# Nu6550.net
KiCad netlist of a schematic drawn in EAGLE
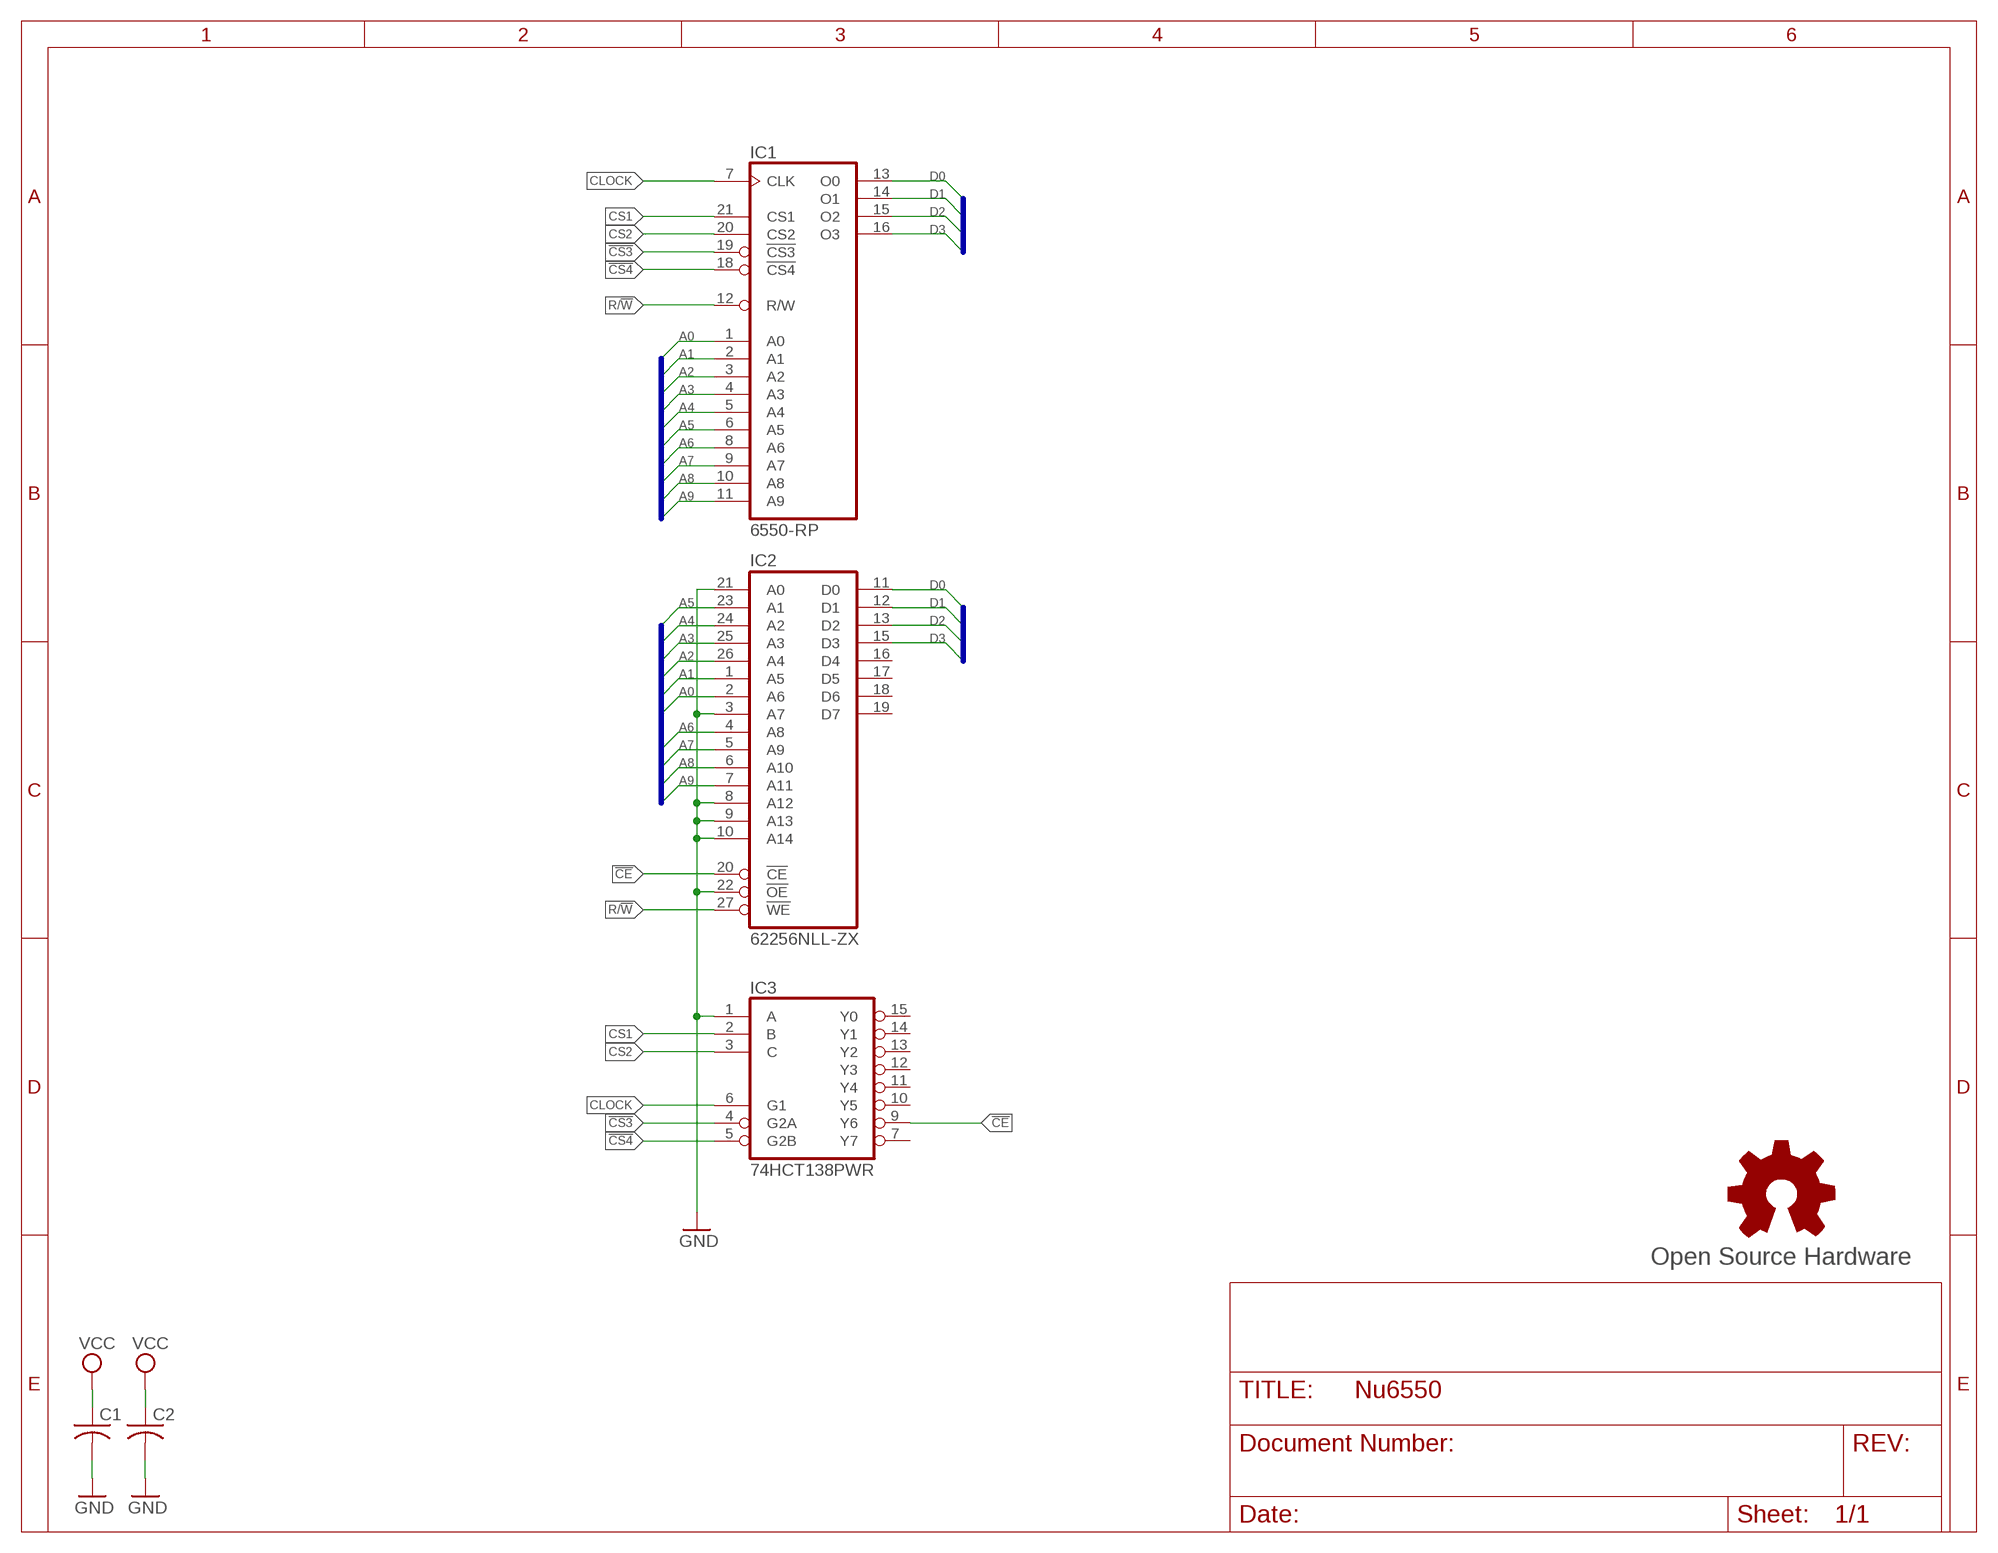
[diagram p0: schematic, sheet 1]

(export (version "E")
  (design (tool "Eeschema 10.0.6"))
  (components
    (comp (ref "C1")
      (value "C-USC0402")
      (footprint "eagle-import:C0402")
      (libsource (lib "eagle-import") (part "C-USC0402"))
    )
    (comp (ref "C2")
      (value "C-USC0402")
      (footprint "eagle-import:C0402")
      (libsource (lib "eagle-import") (part "C-USC0402"))
    )
    (comp (ref "GOLD_ORB_SM1")
      (value "Open Source Hardware")
      (footprint "eagle-import:OSHW_5MM")
      (libsource (lib "eagle-import") (part "OSHWLOGOLOGO5MM"))
    )
    (comp (ref "IC1")
      (value "6550-RP")
      (footprint "eagle-import:DIL22_4-ROUNDPAD")
      (libsource (lib "eagle-import") (part "6550-RP"))
    )
    (comp (ref "IC2")
      (value "62256NLL-ZX")
      (footprint "eagle-import:TSOP1-28")
      (libsource (lib "eagle-import") (part "JEDEC_32KB_SRAMZX"))
    )
    (comp (ref "IC3")
      (value "74HCT138PWR")
      (footprint "eagle-import:TSSOP16")
      (libsource (lib "eagle-import") (part "74138PWRHCT"))
    )
  )
  (nets
    (net (code "1") (name "/A0") (class "Default")
      (node (ref "IC1") (pin "1") (pinfunction "A0_1") (pintype "input"))
      (node (ref "IC2") (pin "2") (pinfunction "A6_2") (pintype "input"))
    )
    (net (code "2") (name "/A1") (class "Default")
      (node (ref "IC1") (pin "2") (pinfunction "A1_2") (pintype "input"))
      (node (ref "IC2") (pin "1") (pinfunction "A5_1") (pintype "input"))
    )
    (net (code "3") (name "/A2") (class "Default")
      (node (ref "IC1") (pin "3") (pinfunction "A2_3") (pintype "input"))
      (node (ref "IC2") (pin "26") (pinfunction "A4_26") (pintype "input"))
    )
    (net (code "4") (name "/A3") (class "Default")
      (node (ref "IC1") (pin "4") (pinfunction "A3_4") (pintype "input"))
      (node (ref "IC2") (pin "25") (pinfunction "A3_25") (pintype "input"))
    )
    (net (code "5") (name "/A4") (class "Default")
      (node (ref "IC1") (pin "5") (pinfunction "A4_5") (pintype "input"))
      (node (ref "IC2") (pin "24") (pinfunction "A2_24") (pintype "input"))
    )
    (net (code "6") (name "/A5") (class "Default")
      (node (ref "IC1") (pin "6") (pinfunction "A5_6") (pintype "input"))
      (node (ref "IC2") (pin "23") (pinfunction "A1_23") (pintype "input"))
    )
    (net (code "7") (name "/A6") (class "Default")
      (node (ref "IC1") (pin "8") (pinfunction "A6_8") (pintype "input"))
      (node (ref "IC2") (pin "4") (pinfunction "A8_4") (pintype "input"))
    )
    (net (code "8") (name "/A7") (class "Default")
      (node (ref "IC1") (pin "9") (pinfunction "A7_9") (pintype "input"))
      (node (ref "IC2") (pin "5") (pinfunction "A9_5") (pintype "input"))
    )
    (net (code "9") (name "/A8") (class "Default")
      (node (ref "IC1") (pin "10") (pinfunction "A8_10") (pintype "input"))
      (node (ref "IC2") (pin "6") (pinfunction "A10_6") (pintype "input"))
    )
    (net (code "10") (name "/A9") (class "Default")
      (node (ref "IC1") (pin "11") (pinfunction "A9_11") (pintype "input"))
      (node (ref "IC2") (pin "7") (pinfunction "A11_7") (pintype "input"))
    )
    (net (code "11") (name "/D0") (class "Default")
      (node (ref "IC1") (pin "13") (pinfunction "O0_13") (pintype "tri_state"))
      (node (ref "IC2") (pin "11") (pinfunction "D0_11") (pintype "bidirectional"))
    )
    (net (code "12") (name "/D1") (class "Default")
      (node (ref "IC1") (pin "14") (pinfunction "O1_14") (pintype "tri_state"))
      (node (ref "IC2") (pin "12") (pinfunction "D1_12") (pintype "bidirectional"))
    )
    (net (code "13") (name "/D2") (class "Default")
      (node (ref "IC1") (pin "15") (pinfunction "O2_15") (pintype "tri_state"))
      (node (ref "IC2") (pin "13") (pinfunction "D2_13") (pintype "bidirectional"))
    )
    (net (code "14") (name "/D3") (class "Default")
      (node (ref "IC1") (pin "16") (pinfunction "O3_16") (pintype "tri_state"))
      (node (ref "IC2") (pin "15") (pinfunction "D3_15") (pintype "bidirectional"))
    )
    (net (code "15") (name "/R{slash}~{W}") (class "Default")
      (node (ref "IC1") (pin "12") (pinfunction "R/W_12") (pintype "input"))
      (node (ref "IC2") (pin "27") (pinfunction "~{WE}_27") (pintype "input"))
    )
    (net (code "16") (name "/~{CE}") (class "Default")
      (node (ref "IC2") (pin "20") (pinfunction "~{CE}_20") (pintype "input"))
      (node (ref "IC3") (pin "9") (pinfunction "Y6_9") (pintype "output"))
    )
    (net (code "17") (name "/~{CS3}") (class "Default")
      (node (ref "IC1") (pin "19") (pinfunction "~{CS3}_19") (pintype "input"))
      (node (ref "IC3") (pin "4") (pinfunction "G2A_4") (pintype "input"))
    )
    (net (code "18") (name "/~{CS4}") (class "Default")
      (node (ref "IC1") (pin "18") (pinfunction "~{CS4}_18") (pintype "input"))
      (node (ref "IC3") (pin "5") (pinfunction "G2B_5") (pintype "input"))
    )
    (net (code "19") (name "CLOCK") (class "Default")
      (node (ref "IC1") (pin "7") (pinfunction "CLK_7") (pintype "input"))
      (node (ref "IC3") (pin "6") (pinfunction "G1_6") (pintype "input"))
    )
    (net (code "20") (name "CS1") (class "Default")
      (node (ref "IC1") (pin "21") (pinfunction "CS1_21") (pintype "input"))
      (node (ref "IC3") (pin "2") (pinfunction "B_2") (pintype "input"))
    )
    (net (code "21") (name "CS2") (class "Default")
      (node (ref "IC1") (pin "20") (pinfunction "CS2_20") (pintype "input"))
      (node (ref "IC3") (pin "3") (pinfunction "C_3") (pintype "input"))
    )
    (net (code "22") (name "GND") (class "Default")
      (node (ref "C1") (pin "2") (pinfunction "2_2") (pintype "passive"))
      (node (ref "C2") (pin "2") (pinfunction "2_2") (pintype "passive"))
      (node (ref "IC2") (pin "10") (pinfunction "A14_10") (pintype "input"))
      (node (ref "IC2") (pin "21") (pinfunction "A0_21") (pintype "input"))
      (node (ref "IC2") (pin "22") (pinfunction "~{OE}_22") (pintype "input"))
      (node (ref "IC2") (pin "3") (pinfunction "A7_3") (pintype "input"))
      (node (ref "IC2") (pin "8") (pinfunction "A12_8") (pintype "input"))
      (node (ref "IC2") (pin "9") (pinfunction "A13_9") (pintype "input"))
      (node (ref "IC3") (pin "1") (pinfunction "A_1") (pintype "input"))
    )
    (net (code "23") (name "VCC") (class "Default")
      (node (ref "C1") (pin "1") (pinfunction "1_1") (pintype "passive"))
      (node (ref "C2") (pin "1") (pinfunction "1_1") (pintype "passive"))
    )
    (net (code "24") (name "unconnected-(IC2A-D4-Pad16)") (class "Default")
      (node (ref "IC2") (pin "16") (pinfunction "D4_16") (pintype "bidirectional"))
    )
    (net (code "25") (name "unconnected-(IC2A-D5-Pad17)") (class "Default")
      (node (ref "IC2") (pin "17") (pinfunction "D5_17") (pintype "bidirectional"))
    )
    (net (code "26") (name "unconnected-(IC2A-D6-Pad18)") (class "Default")
      (node (ref "IC2") (pin "18") (pinfunction "D6_18") (pintype "bidirectional"))
    )
    (net (code "27") (name "unconnected-(IC2A-D7-Pad19)") (class "Default")
      (node (ref "IC2") (pin "19") (pinfunction "D7_19") (pintype "bidirectional"))
    )
    (net (code "28") (name "unconnected-(IC3A-Y0-Pad15)") (class "Default")
      (node (ref "IC3") (pin "15") (pinfunction "Y0_15") (pintype "output"))
    )
    (net (code "29") (name "unconnected-(IC3A-Y1-Pad14)") (class "Default")
      (node (ref "IC3") (pin "14") (pinfunction "Y1_14") (pintype "output"))
    )
    (net (code "30") (name "unconnected-(IC3A-Y2-Pad13)") (class "Default")
      (node (ref "IC3") (pin "13") (pinfunction "Y2_13") (pintype "output"))
    )
    (net (code "31") (name "unconnected-(IC3A-Y3-Pad12)") (class "Default")
      (node (ref "IC3") (pin "12") (pinfunction "Y3_12") (pintype "output"))
    )
    (net (code "32") (name "unconnected-(IC3A-Y4-Pad11)") (class "Default")
      (node (ref "IC3") (pin "11") (pinfunction "Y4_11") (pintype "output"))
    )
    (net (code "33") (name "unconnected-(IC3A-Y5-Pad10)") (class "Default")
      (node (ref "IC3") (pin "10") (pinfunction "Y5_10") (pintype "output"))
    )
    (net (code "34") (name "unconnected-(IC3A-Y7-Pad7)") (class "Default")
      (node (ref "IC3") (pin "7") (pinfunction "Y7_7") (pintype "output"))
    )
  )
)
